# MCU_Board.net
KiCad netlist of a schematic drawn in Altium Designer
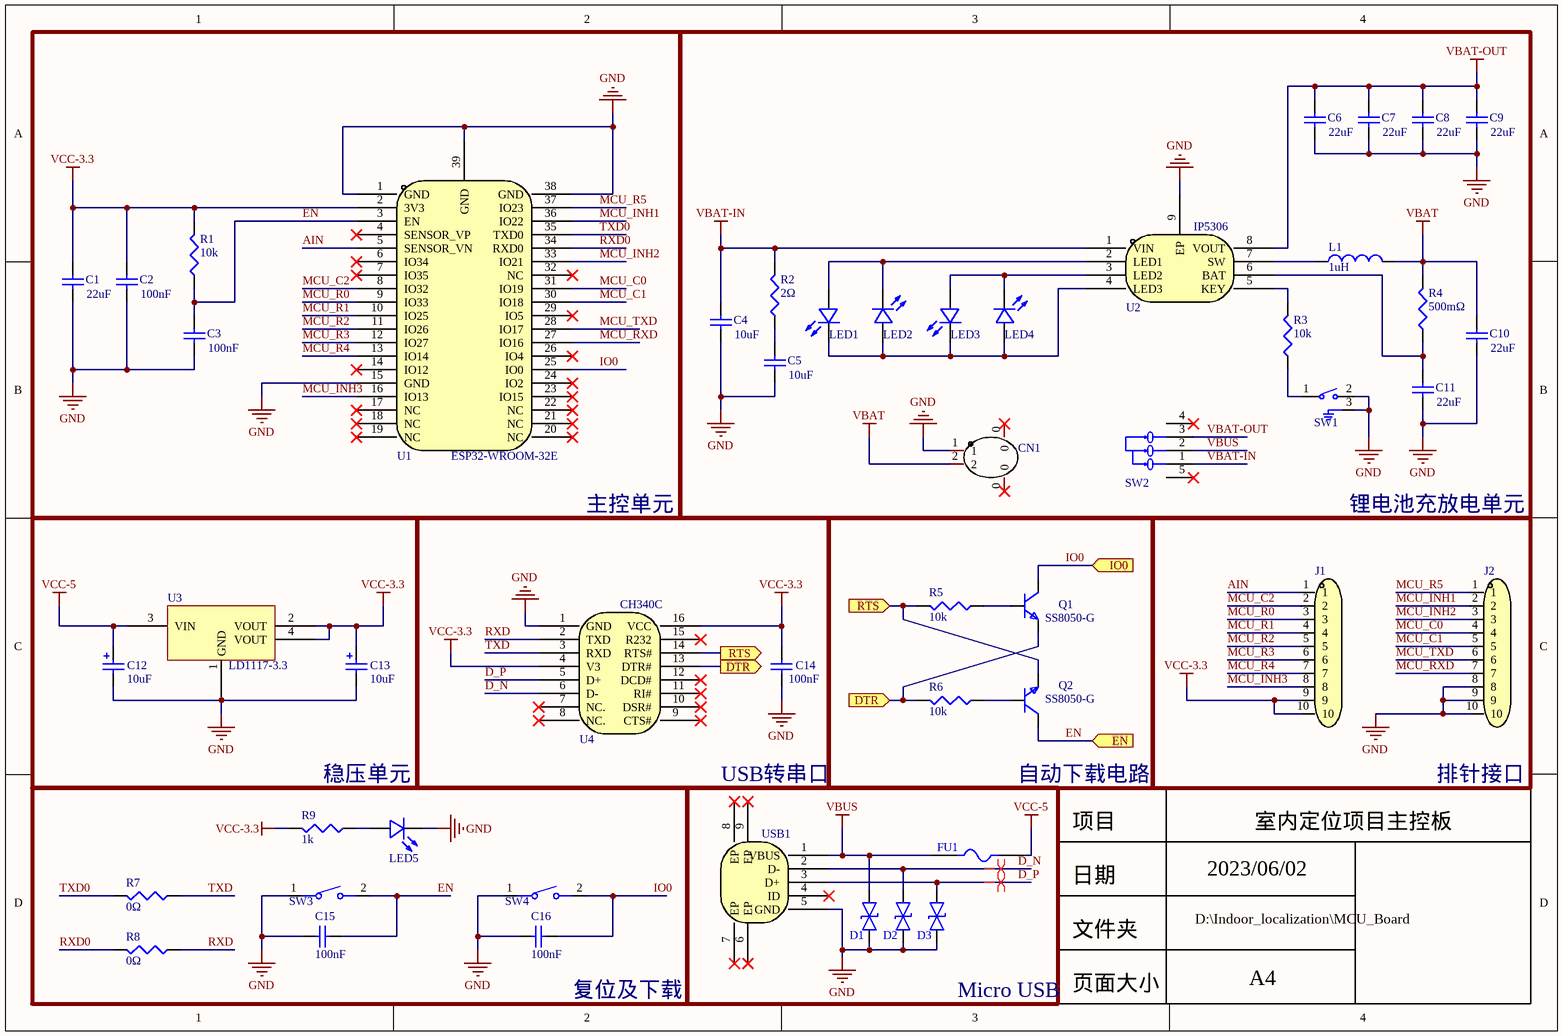
[diagram p0: MCU_Board.SchDoc]

(export (version "E")
  (design (tool "Eeschema 10.0.6"))
  (components
    (comp (ref "C1")
      (value "22uF")
      (footprint "C0603")
      (description "Capacitor")
      (fields (field (name "Comment") "Cap") (field (name "PUBLISHER") "Altium Limited"))
      (libsource (lib "Miscellaneous Devices") (part "Cap"))
    )
    (comp (ref "C2")
      (value "100nF")
      (footprint "C0603")
      (description "Capacitor")
      (fields (field (name "Comment") "Cap") (field (name "PUBLISHER") "Altium Limited"))
      (libsource (lib "Miscellaneous Devices") (part "Cap"))
    )
    (comp (ref "C3")
      (value "100nF")
      (footprint "C0603")
      (description "Capacitor")
      (fields (field (name "Comment") "Cap") (field (name "PUBLISHER") "Altium Limited"))
      (libsource (lib "Miscellaneous Devices") (part "Cap"))
    )
    (comp (ref "C4")
      (value "10uF")
      (footprint "C0603")
      (description "Capacitor")
      (fields (field (name "Comment") "Cap") (field (name "PUBLISHER") "Altium Limited"))
      (libsource (lib "Miscellaneous Devices") (part "Cap"))
    )
    (comp (ref "C5")
      (value "10uF")
      (footprint "C0603")
      (description "Capacitor")
      (fields (field (name "Comment") "Cap") (field (name "PUBLISHER") "Altium Limited"))
      (libsource (lib "Miscellaneous Devices") (part "Cap"))
    )
    (comp (ref "C6")
      (value "22uF")
      (footprint "C1206")
      (description "Capacitor")
      (fields (field (name "Comment") "Cap") (field (name "PUBLISHER") "Altium Limited"))
      (libsource (lib "Miscellaneous Devices") (part "Cap"))
    )
    (comp (ref "C7")
      (value "22uF")
      (footprint "C1206")
      (description "Capacitor")
      (fields (field (name "Comment") "Cap") (field (name "PUBLISHER") "Altium Limited"))
      (libsource (lib "Miscellaneous Devices") (part "Cap"))
    )
    (comp (ref "C8")
      (value "22uF")
      (footprint "C1206")
      (description "Capacitor")
      (fields (field (name "Comment") "Cap") (field (name "PUBLISHER") "Altium Limited"))
      (libsource (lib "Miscellaneous Devices") (part "Cap"))
    )
    (comp (ref "C9")
      (value "22uF")
      (footprint "C1206")
      (description "Capacitor")
      (fields (field (name "Comment") "Cap") (field (name "PUBLISHER") "Altium Limited"))
      (libsource (lib "Miscellaneous Devices") (part "Cap"))
    )
    (comp (ref "C10")
      (value "22uF")
      (footprint "C1206")
      (description "Capacitor")
      (fields (field (name "Comment") "Cap") (field (name "PUBLISHER") "Altium Limited"))
      (libsource (lib "Miscellaneous Devices") (part "Cap"))
    )
    (comp (ref "C11")
      (value "22uF")
      (footprint "C1206")
      (description "Capacitor")
      (fields (field (name "Comment") "Cap") (field (name "PUBLISHER") "Altium Limited"))
      (libsource (lib "Miscellaneous Devices") (part "Cap"))
    )
    (comp (ref "C12")
      (value "10uF")
      (footprint "CAP-SMD_L3.2-W1.6-RD-C7171")
      (description "贴片钽电容")
      (fields (field (name "MANUFACTURER") "Kyocera AVX") (field (name "MANUFACTURER PART") "TAJA106K016RNJ"))
      (libsource (lib "Passive_Device") (part "Cap-TAJA"))
    )
    (comp (ref "C13")
      (value "10uF")
      (footprint "CAP-SMD_L3.2-W1.6-RD-C7171")
      (description "贴片钽电容")
      (fields (field (name "MANUFACTURER") "Kyocera AVX") (field (name "MANUFACTURER PART") "TAJA106K016RNJ"))
      (libsource (lib "Passive_Device") (part "Cap-TAJA"))
    )
    (comp (ref "C14")
      (value "100nF")
      (footprint "C0603")
      (description "Capacitor")
      (fields (field (name "Comment") "Cap") (field (name "PUBLISHER") "Altium Limited"))
      (libsource (lib "Miscellaneous Devices") (part "Cap"))
    )
    (comp (ref "C15")
      (value "100nF")
      (footprint "C0603")
      (description "Capacitor")
      (fields (field (name "Comment") "Cap") (field (name "PUBLISHER") "Altium Limited"))
      (libsource (lib "Miscellaneous Devices") (part "Cap"))
    )
    (comp (ref "C16")
      (value "100nF")
      (footprint "C0603")
      (description "Capacitor")
      (fields (field (name "Comment") "Cap") (field (name "PUBLISHER") "Altium Limited"))
      (libsource (lib "Miscellaneous Devices") (part "Cap"))
    )
    (comp (ref "CN1")
      (value "1.0T-2P卧贴")
      (footprint "CONN-SMD_1.0T-2P")
      (description "锂电池接口")
      (fields (field (name "MANUFACTURER") "BOOMELE(博穆精密)"))
      (libsource (lib "Component") (part "1.0T-2P卧贴"))
    )
    (comp (ref "D1")
      (value "LESD5D5.0CT1G")
      (footprint "SOD-523_L1.2-W0.8-LS1.6-BI")
      (description "静电放电(ESD)保护器件")
      (fields (field (name "DESIGNER") "U?"))
      (libsource (lib "Passive_Device") (part "LESD5D5.0CT1G"))
    )
    (comp (ref "D2")
      (value "LESD5D5.0CT1G")
      (footprint "SOD-523_L1.2-W0.8-LS1.6-BI")
      (description "静电放电(ESD)保护器件")
      (fields (field (name "DESIGNER") "U?"))
      (libsource (lib "Passive_Device") (part "LESD5D5.0CT1G"))
    )
    (comp (ref "D3")
      (value "LESD5D5.0CT1G")
      (footprint "SOD-523_L1.2-W0.8-LS1.6-BI")
      (description "静电放电(ESD)保护器件")
      (fields (field (name "DESIGNER") "U?"))
      (libsource (lib "Passive_Device") (part "LESD5D5.0CT1G"))
    )
    (comp (ref "FU1")
      (value "FUSE 1A")
      (footprint "F0805")
      (description "贴片保险丝")
      (fields (field (name "MANUFACTURER") "RUILON(瑞隆源)") (field (name "MANUFACTURER PART") "SMD0805P075TF"))
      (libsource (lib "Passive_Device") (part "FU"))
    )
    (comp (ref "J1")
      (value "Header 10X1")
      (footprint "HDR-TH_10P-P2.54-V-M")
      (description "10P*1接插件")
      (fields (field (name "DESIGNER") "U?"))
      (libsource (lib "Connector") (part "Header 10X1"))
    )
    (comp (ref "J2")
      (value "Header 10X1")
      (footprint "HDR-TH_10P-P2.54-V-M")
      (description "10P*1接插件")
      (fields (field (name "DESIGNER") "U?"))
      (libsource (lib "Connector") (part "Header 10X1"))
    )
    (comp (ref "L1")
      (value "1uH")
      (footprint "IND-SMD_L6.5-W6.5_IHLP-2525")
      (description "Inductor")
      (fields (field (name "PUBLISHER") "Altium Limited"))
      (libsource (lib "Miscellaneous Devices") (part "Inductor"))
    )
    (comp (ref "LED1")
      (value "NCD0603G2")
      (footprint "LED0603-RD")
      (fields (field (name "MANUFACTURER") "国星光电"))
      (libsource (lib "Component") (part "NCD0603G2"))
    )
    (comp (ref "LED2")
      (value "NCD0603G2")
      (footprint "LED0603-RD")
      (fields (field (name "MANUFACTURER") "国星光电"))
      (libsource (lib "Component") (part "NCD0603G2"))
    )
    (comp (ref "LED3")
      (value "NCD0603G2")
      (footprint "LED0603-RD")
      (fields (field (name "MANUFACTURER") "国星光电"))
      (libsource (lib "Component") (part "NCD0603G2"))
    )
    (comp (ref "LED4")
      (value "NCD0603G2")
      (footprint "LED0603-RD")
      (fields (field (name "MANUFACTURER") "国星光电"))
      (libsource (lib "Component") (part "NCD0603G2"))
    )
    (comp (ref "LED5")
      (value "NCD0603G2")
      (footprint "LED0603-RD")
      (description "LED")
      (fields (field (name "MANUFACTURER") "国星光电"))
      (libsource (lib "Component") (part "NCD0603G2"))
    )
    (comp (ref "Q1")
      (value "SS8050-G")
      (footprint "SOT-23-3_L2.9-W1.3-P1.90-LS2.4-BR")
      (fields (field (name "MANUFACTURER") "CJ(江苏长电/长晶)"))
      (libsource (lib "Component") (part "SS8050-G"))
    )
    (comp (ref "Q2")
      (value "SS8050-G")
      (footprint "SOT-23-3_L2.9-W1.3-P1.90-LS2.4-BR")
      (fields (field (name "MANUFACTURER") "CJ(江苏长电/长晶)"))
      (libsource (lib "Component") (part "SS8050-G"))
    )
    (comp (ref "R1")
      (value "10k")
      (footprint "R0603")
      (description "Resistor")
      (fields (field (name "PUBLISHER") "Altium Limited"))
      (libsource (lib "Miscellaneous Devices") (part "Res3"))
    )
    (comp (ref "R2")
      (value "2Ω")
      (footprint "R0603")
      (description "Resistor")
      (fields (field (name "PUBLISHER") "Altium Limited"))
      (libsource (lib "Miscellaneous Devices") (part "Res3"))
    )
    (comp (ref "R3")
      (value "10k")
      (footprint "R0603")
      (description "Resistor")
      (fields (field (name "PUBLISHER") "Altium Limited"))
      (libsource (lib "Miscellaneous Devices") (part "Res3"))
    )
    (comp (ref "R4")
      (value "500mΩ")
      (footprint "R0603")
      (description "Resistor")
      (fields (field (name "PUBLISHER") "Altium Limited"))
      (libsource (lib "Miscellaneous Devices") (part "Res3"))
    )
    (comp (ref "R5")
      (value "10k")
      (footprint "R0603")
      (description "Resistor")
      (fields (field (name "PUBLISHER") "Altium Limited"))
      (libsource (lib "Miscellaneous Devices") (part "Res3"))
    )
    (comp (ref "R6")
      (value "10k")
      (footprint "R0603")
      (description "Resistor")
      (fields (field (name "PUBLISHER") "Altium Limited"))
      (libsource (lib "Miscellaneous Devices") (part "Res3"))
    )
    (comp (ref "R7")
      (value "0Ω")
      (footprint "R0603")
      (description "Resistor")
      (fields (field (name "PUBLISHER") "Altium Limited"))
      (libsource (lib "Miscellaneous Devices") (part "Res3"))
    )
    (comp (ref "R8")
      (value "0Ω")
      (footprint "R0603")
      (description "Resistor")
      (fields (field (name "PUBLISHER") "Altium Limited"))
      (libsource (lib "Miscellaneous Devices") (part "Res3"))
    )
    (comp (ref "R9")
      (value "1k")
      (footprint "R0603")
      (description "Resistor")
      (fields (field (name "PUBLISHER") "Altium Limited"))
      (libsource (lib "Miscellaneous Devices") (part "Res3"))
    )
    (comp (ref "SW1")
      (value "GT-TCB73B-H048-L1")
      (footprint "SW-TH_G-SWITCH_GT-TCB73B-H048-L1")
      (fields (field (name "MANUFACTURER") "G-Switch(品赞)"))
      (libsource (lib "Component") (part "GT-TCB73B-H048-L1"))
    )
    (comp (ref "SW2")
      (value "SK12D07VG3")
      (footprint "SW-TH_SK12D07VG3")
      (fields (field (name "MANUFACTURER") "SHOU HAN(首韩)"))
      (libsource (lib "Component") (part "SK12D07VG3"))
    )
    (comp (ref "SW3")
      (value "TS-1088-AR02016")
      (footprint "SW-SMD_L3.9-W3.0-P4.45")
      (fields (field (name "MANUFACTURER") "XUNPU(讯普)"))
      (libsource (lib "Component") (part "TS-1088-AR02016"))
    )
    (comp (ref "SW4")
      (value "TS-1088-AR02016")
      (footprint "SW-SMD_L3.9-W3.0-P4.45")
      (fields (field (name "MANUFACTURER") "XUNPU(讯普)"))
      (libsource (lib "Component") (part "TS-1088-AR02016"))
    )
    (comp (ref "U1")
      (value "ESP32-WROOM-32E")
      (footprint "WIFI-SMD_ESP32-WROOM-32E")
      (fields
        (field (name "MANUFACTURER") "ESPRESSIF(乐鑫)")
        (field (name "MANUFACTURER PART") "ESP32-WROOM-32E-N16")
      )
      (libsource (lib "Component") (part "ESP32-WROOM-32E-N16_C701343"))
    )
    (comp (ref "U2")
      (value "IP5306")
      (footprint "ESOP-8_L4.9-W3.9-P1.27-LS6.0-BL-EP")
      (fields (field (name "MANUFACTURER") "INJOINIC(英集芯)"))
      (libsource (lib "Component") (part "IP5306"))
    )
    (comp (ref "U3")
      (value "LD1117-3.3")
      (footprint "SOT-223-3_L6.5-W3.4-P2.30-LS7.0-BR")
      (description "低压差线性稳压器3.3V")
      (libsource (lib "Power") (part "LD1117-3.3"))
    )
    (comp (ref "U4")
      (value "CH340C")
      (footprint "SOP-16_L10.0-W3.9-P1.27-LS6.0-BL")
      (fields (field (name "MANUFACTURER") "WCH(南京沁恒)"))
      (libsource (lib "Component") (part "CH340C"))
    )
    (comp (ref "USB1")
      (value "U-F-M5DD-W-2")
      (footprint "MICRO-USB-SMD_MICRO-USB-A17")
      (fields (field (name "MANUFACTURER") "韩国韩荣"))
      (libsource (lib "Component") (part "U-F-M5DD-W-2"))
    )
  )
  (nets
    (net (code "2") (name "/AIN") (class "Default")
      (node (ref "J1") (pin "1") (pinfunction "1_1") (pintype "passive"))
      (node (ref "U1") (pin "5") (pinfunction "SENSOR_VN_5") (pintype "passive"))
    )
    (net (code "3") (name "/DTR") (class "Default")
      (node (ref "Q1") (pin "2") (pinfunction "E_2") (pintype "passive"))
      (node (ref "R6") (pin "2") (pinfunction "2_2") (pintype "passive"))
      (node (ref "U4") (pin "13") (pinfunction "DTR#_13") (pintype "passive"))
    )
    (net (code "4") (name "/D_N") (class "Default")
      (node (ref "D2") (pin "2") (pinfunction "2_2") (pintype "passive"))
      (node (ref "U4") (pin "6") (pinfunction "D-_6") (pintype "passive"))
      (node (ref "USB1") (pin "2") (pinfunction "D-_2") (pintype "passive"))
    )
    (net (code "5") (name "/D_P") (class "Default")
      (node (ref "D3") (pin "2") (pinfunction "2_2") (pintype "passive"))
      (node (ref "U4") (pin "5") (pinfunction "D+_5") (pintype "passive"))
      (node (ref "USB1") (pin "3") (pinfunction "D+_3") (pintype "passive"))
    )
    (net (code "6") (name "/EN") (class "Default")
      (node (ref "C15") (pin "1") (pinfunction "1_1") (pintype "passive"))
      (node (ref "C3") (pin "2") (pinfunction "2_2") (pintype "passive"))
      (node (ref "Q2") (pin "3") (pinfunction "C_3") (pintype "passive"))
      (node (ref "R1") (pin "1") (pinfunction "1_1") (pintype "passive"))
      (node (ref "SW3") (pin "2") (pinfunction "2_2") (pintype "passive"))
      (node (ref "U1") (pin "3") (pinfunction "EN_3") (pintype "passive"))
    )
    (net (code "7") (name "/IO0") (class "Default")
      (node (ref "C16") (pin "1") (pinfunction "1_1") (pintype "passive"))
      (node (ref "Q1") (pin "3") (pinfunction "C_3") (pintype "passive"))
      (node (ref "SW4") (pin "2") (pinfunction "2_2") (pintype "passive"))
      (node (ref "U1") (pin "25") (pinfunction "IO0_25") (pintype "passive"))
    )
    (net (code "8") (name "/MCU_C0") (class "Default")
      (node (ref "J2") (pin "4") (pinfunction "4_4") (pintype "passive"))
      (node (ref "U1") (pin "31") (pinfunction "IO19_31") (pintype "passive"))
    )
    (net (code "9") (name "/MCU_C1") (class "Default")
      (node (ref "J2") (pin "5") (pinfunction "5_5") (pintype "passive"))
      (node (ref "U1") (pin "30") (pinfunction "IO18_30") (pintype "passive"))
    )
    (net (code "10") (name "/MCU_C2") (class "Default")
      (node (ref "J1") (pin "2") (pinfunction "2_2") (pintype "passive"))
      (node (ref "U1") (pin "8") (pinfunction "IO32_8") (pintype "passive"))
    )
    (net (code "11") (name "/MCU_INH1") (class "Default")
      (node (ref "J2") (pin "2") (pinfunction "2_2") (pintype "passive"))
      (node (ref "U1") (pin "36") (pinfunction "IO22_36") (pintype "passive"))
    )
    (net (code "12") (name "/MCU_INH2") (class "Default")
      (node (ref "J2") (pin "3") (pinfunction "3_3") (pintype "passive"))
      (node (ref "U1") (pin "33") (pinfunction "IO21_33") (pintype "passive"))
    )
    (net (code "13") (name "/MCU_INH3") (class "Default")
      (node (ref "J1") (pin "8") (pinfunction "8_8") (pintype "passive"))
      (node (ref "U1") (pin "16") (pinfunction "IO13_16") (pintype "passive"))
    )
    (net (code "14") (name "/MCU_R0") (class "Default")
      (node (ref "J1") (pin "3") (pinfunction "3_3") (pintype "passive"))
      (node (ref "U1") (pin "9") (pinfunction "IO33_9") (pintype "passive"))
    )
    (net (code "15") (name "/MCU_R1") (class "Default")
      (node (ref "J1") (pin "4") (pinfunction "4_4") (pintype "passive"))
      (node (ref "U1") (pin "10") (pinfunction "IO25_10") (pintype "passive"))
    )
    (net (code "16") (name "/MCU_R2") (class "Default")
      (node (ref "J1") (pin "5") (pinfunction "5_5") (pintype "passive"))
      (node (ref "U1") (pin "11") (pinfunction "IO26_11") (pintype "passive"))
    )
    (net (code "17") (name "/MCU_R3") (class "Default")
      (node (ref "J1") (pin "6") (pinfunction "6_6") (pintype "passive"))
      (node (ref "U1") (pin "12") (pinfunction "IO27_12") (pintype "passive"))
    )
    (net (code "18") (name "/MCU_R4") (class "Default")
      (node (ref "J1") (pin "7") (pinfunction "7_7") (pintype "passive"))
      (node (ref "U1") (pin "13") (pinfunction "IO14_13") (pintype "passive"))
    )
    (net (code "19") (name "/MCU_R5") (class "Default")
      (node (ref "J2") (pin "1") (pinfunction "1_1") (pintype "passive"))
      (node (ref "U1") (pin "37") (pinfunction "IO23_37") (pintype "passive"))
    )
    (net (code "20") (name "/MCU_RXD") (class "Default")
      (node (ref "J2") (pin "7") (pinfunction "7_7") (pintype "passive"))
      (node (ref "U1") (pin "27") (pinfunction "IO16_27") (pintype "passive"))
    )
    (net (code "21") (name "/MCU_TXD") (class "Default")
      (node (ref "J2") (pin "6") (pinfunction "6_6") (pintype "passive"))
      (node (ref "U1") (pin "28") (pinfunction "IO17_28") (pintype "passive"))
    )
    (net (code "22") (name "/RTS") (class "Default")
      (node (ref "Q2") (pin "2") (pinfunction "E_2") (pintype "passive"))
      (node (ref "R5") (pin "2") (pinfunction "2_2") (pintype "passive"))
      (node (ref "U4") (pin "14") (pinfunction "RTS#_14") (pintype "passive"))
    )
    (net (code "23") (name "/RXD") (class "Default")
      (node (ref "R8") (pin "1") (pinfunction "1_1") (pintype "passive"))
      (node (ref "U4") (pin "2") (pinfunction "TXD_2") (pintype "passive"))
    )
    (net (code "24") (name "/RXD0") (class "Default")
      (node (ref "R8") (pin "2") (pinfunction "2_2") (pintype "passive"))
      (node (ref "U1") (pin "34") (pinfunction "RXD0_34") (pintype "passive"))
    )
    (net (code "25") (name "/TXD") (class "Default")
      (node (ref "R7") (pin "1") (pinfunction "1_1") (pintype "passive"))
      (node (ref "U4") (pin "3") (pinfunction "RXD_3") (pintype "passive"))
    )
    (net (code "26") (name "/TXD0") (class "Default")
      (node (ref "R7") (pin "2") (pinfunction "2_2") (pintype "passive"))
      (node (ref "U1") (pin "35") (pinfunction "TXD0_35") (pintype "passive"))
    )
    (net (code "27") (name "GND") (class "Default")
      (node (ref "C1") (pin "1") (pinfunction "1_1") (pintype "passive"))
      (node (ref "C10") (pin "1") (pinfunction "1_1") (pintype "passive"))
      (node (ref "C11") (pin "1") (pinfunction "1_1") (pintype "passive"))
      (node (ref "C12") (pin "2") (pinfunction "2_2") (pintype "passive"))
      (node (ref "C13") (pin "2") (pinfunction "2_2") (pintype "passive"))
      (node (ref "C14") (pin "2") (pinfunction "2_2") (pintype "passive"))
      (node (ref "C15") (pin "2") (pinfunction "2_2") (pintype "passive"))
      (node (ref "C16") (pin "2") (pinfunction "2_2") (pintype "passive"))
      (node (ref "C2") (pin "1") (pinfunction "1_1") (pintype "passive"))
      (node (ref "C3") (pin "1") (pinfunction "1_1") (pintype "passive"))
      (node (ref "C4") (pin "1") (pinfunction "1_1") (pintype "passive"))
      (node (ref "C5") (pin "1") (pinfunction "1_1") (pintype "passive"))
      (node (ref "C6") (pin "1") (pinfunction "1_1") (pintype "passive"))
      (node (ref "C7") (pin "1") (pinfunction "1_1") (pintype "passive"))
      (node (ref "C8") (pin "1") (pinfunction "1_1") (pintype "passive"))
      (node (ref "C9") (pin "1") (pinfunction "1_1") (pintype "passive"))
      (node (ref "CN1") (pin "1") (pinfunction "1_1") (pintype "passive"))
      (node (ref "D1") (pin "1") (pinfunction "1_1") (pintype "passive"))
      (node (ref "D2") (pin "1") (pinfunction "1_1") (pintype "passive"))
      (node (ref "D3") (pin "1") (pinfunction "1_1") (pintype "passive"))
      (node (ref "J2") (pin "10") (pinfunction "10_10") (pintype "passive"))
      (node (ref "J2") (pin "8") (pinfunction "8_8") (pintype "passive"))
      (node (ref "J2") (pin "9") (pinfunction "9_9") (pintype "passive"))
      (node (ref "LED5") (pin "1") (pinfunction "K_1") (pintype "passive"))
      (node (ref "SW1") (pin "2") (pinfunction "2_2") (pintype "passive"))
      (node (ref "SW1") (pin "3") (pinfunction "3_3") (pintype "passive"))
      (node (ref "SW3") (pin "1") (pinfunction "1_1") (pintype "passive"))
      (node (ref "SW4") (pin "1") (pinfunction "1_1") (pintype "passive"))
      (node (ref "U1") (pin "1") (pinfunction "GND_1") (pintype "passive"))
      (node (ref "U1") (pin "15") (pinfunction "GND_15") (pintype "passive"))
      (node (ref "U1") (pin "38") (pinfunction "GND_38") (pintype "passive"))
      (node (ref "U1") (pin "39") (pinfunction "GND_39") (pintype "passive"))
      (node (ref "U2") (pin "9") (pinfunction "EP_9") (pintype "passive"))
      (node (ref "U3") (pin "1") (pinfunction "GND_1") (pintype "passive"))
      (node (ref "U4") (pin "1") (pinfunction "GND_1") (pintype "passive"))
      (node (ref "USB1") (pin "5") (pinfunction "GND_5") (pintype "passive"))
    )
    (net (code "28") (name "Net-(C5-Pad2)") (class "Default")
      (node (ref "C5") (pin "2") (pinfunction "2_2") (pintype "passive"))
      (node (ref "R2") (pin "1") (pinfunction "1_1") (pintype "passive"))
    )
    (net (code "29") (name "Net-(LED1-A)") (class "Default")
      (node (ref "LED1") (pin "2") (pinfunction "A_2") (pintype "passive"))
      (node (ref "LED2") (pin "1") (pinfunction "K_1") (pintype "passive"))
      (node (ref "U2") (pin "2") (pinfunction "LED1_2") (pintype "passive"))
    )
    (net (code "30") (name "Net-(LED1-K)") (class "Default")
      (node (ref "LED1") (pin "1") (pinfunction "K_1") (pintype "passive"))
      (node (ref "LED2") (pin "2") (pinfunction "A_2") (pintype "passive"))
      (node (ref "LED3") (pin "1") (pinfunction "K_1") (pintype "passive"))
      (node (ref "LED4") (pin "2") (pinfunction "A_2") (pintype "passive"))
      (node (ref "U2") (pin "4") (pinfunction "LED3_4") (pintype "passive"))
    )
    (net (code "31") (name "Net-(LED3-A)") (class "Default")
      (node (ref "LED3") (pin "2") (pinfunction "A_2") (pintype "passive"))
      (node (ref "LED4") (pin "1") (pinfunction "K_1") (pintype "passive"))
      (node (ref "U2") (pin "3") (pinfunction "LED2_3") (pintype "passive"))
    )
    (net (code "32") (name "Net-(LED5-A)") (class "Default")
      (node (ref "LED5") (pin "2") (pinfunction "A_2") (pintype "passive"))
      (node (ref "R9") (pin "1") (pinfunction "1_1") (pintype "passive"))
    )
    (net (code "33") (name "Net-(Q1-B)") (class "Default")
      (node (ref "Q1") (pin "1") (pinfunction "B_1") (pintype "passive"))
      (node (ref "R5") (pin "1") (pinfunction "1_1") (pintype "passive"))
    )
    (net (code "34") (name "Net-(Q2-B)") (class "Default")
      (node (ref "Q2") (pin "1") (pinfunction "B_1") (pintype "passive"))
      (node (ref "R6") (pin "1") (pinfunction "1_1") (pintype "passive"))
    )
    (net (code "35") (name "Net-(R3-Pad1)") (class "Default")
      (node (ref "R3") (pin "1") (pinfunction "1_1") (pintype "passive"))
      (node (ref "SW1") (pin "1") (pinfunction "1_1") (pintype "passive"))
    )
    (net (code "36") (name "Net-(U2-BAT)") (class "Default")
      (node (ref "C11") (pin "2") (pinfunction "2_2") (pintype "passive"))
      (node (ref "R4") (pin "1") (pinfunction "1_1") (pintype "passive"))
      (node (ref "U2") (pin "6") (pinfunction "BAT_6") (pintype "passive"))
    )
    (net (code "37") (name "Net-(U2-KEY)") (class "Default")
      (node (ref "R3") (pin "2") (pinfunction "2_2") (pintype "passive"))
      (node (ref "U2") (pin "5") (pinfunction "KEY_5") (pintype "passive"))
    )
    (net (code "38") (name "Net-(U2-SW)") (class "Default")
      (node (ref "L1") (pin "1") (pinfunction "1_1") (pintype "passive"))
      (node (ref "U2") (pin "7") (pinfunction "SW_7") (pintype "passive"))
    )
    (net (code "39") (name "VBAT") (class "Default")
      (node (ref "C10") (pin "2") (pinfunction "2_2") (pintype "passive"))
      (node (ref "CN1") (pin "2") (pinfunction "2_2") (pintype "passive"))
      (node (ref "L1") (pin "2") (pinfunction "2_2") (pintype "passive"))
      (node (ref "R4") (pin "2") (pinfunction "2_2") (pintype "passive"))
    )
    (net (code "40") (name "VBAT-IN") (class "Default")
      (node (ref "C4") (pin "2") (pinfunction "2_2") (pintype "passive"))
      (node (ref "R2") (pin "2") (pinfunction "2_2") (pintype "passive"))
      (node (ref "SW2") (pin "1") (pinfunction "1_1") (pintype "passive"))
      (node (ref "U2") (pin "1") (pinfunction "VIN_1") (pintype "passive"))
    )
    (net (code "41") (name "VBAT-OUT") (class "Default")
      (node (ref "C6") (pin "2") (pinfunction "2_2") (pintype "passive"))
      (node (ref "C7") (pin "2") (pinfunction "2_2") (pintype "passive"))
      (node (ref "C8") (pin "2") (pinfunction "2_2") (pintype "passive"))
      (node (ref "C9") (pin "2") (pinfunction "2_2") (pintype "passive"))
      (node (ref "SW2") (pin "3") (pinfunction "3_3") (pintype "passive"))
      (node (ref "U2") (pin "8") (pinfunction "VOUT_8") (pintype "passive"))
    )
    (net (code "42") (name "VBUS") (class "Default")
      (node (ref "D1") (pin "2") (pinfunction "2_2") (pintype "passive"))
      (node (ref "FU1") (pin "1") (pinfunction "1_1") (pintype "passive"))
      (node (ref "SW2") (pin "2") (pinfunction "2_2") (pintype "passive"))
      (node (ref "USB1") (pin "1") (pinfunction "VBUS_1") (pintype "passive"))
    )
    (net (code "43") (name "VCC-3.3") (class "Default")
      (node (ref "C1") (pin "2") (pinfunction "2_2") (pintype "passive"))
      (node (ref "C13") (pin "1") (pinfunction "1_1") (pintype "passive"))
      (node (ref "C14") (pin "1") (pinfunction "1_1") (pintype "passive"))
      (node (ref "C2") (pin "2") (pinfunction "2_2") (pintype "passive"))
      (node (ref "J1") (pin "10") (pinfunction "10_10") (pintype "passive"))
      (node (ref "J1") (pin "9") (pinfunction "9_9") (pintype "passive"))
      (node (ref "R1") (pin "2") (pinfunction "2_2") (pintype "passive"))
      (node (ref "R9") (pin "2") (pinfunction "2_2") (pintype "passive"))
      (node (ref "U1") (pin "2") (pinfunction "3V3_2") (pintype "passive"))
      (node (ref "U3") (pin "2") (pinfunction "VOUT_2") (pintype "passive"))
      (node (ref "U3") (pin "4") (pinfunction "VOUT_4") (pintype "passive"))
      (node (ref "U4") (pin "16") (pinfunction "VCC_16") (pintype "passive"))
      (node (ref "U4") (pin "4") (pinfunction "V3_4") (pintype "passive"))
    )
    (net (code "44") (name "VCC-5") (class "Default")
      (node (ref "C12") (pin "1") (pinfunction "1_1") (pintype "passive"))
      (node (ref "FU1") (pin "2") (pinfunction "2_2") (pintype "passive"))
      (node (ref "U3") (pin "3") (pinfunction "VIN_3") (pintype "passive"))
    )
    (net (code "45") (name "unconnected-(CN1-Pad0)") (class "Default")
      (node (ref "CN1") (pin "0") (pinfunction "0_0") (pintype "passive+no_connect"))
    )
    (net (code "46") (name "unconnected-(CN1-Pad0)_1") (class "Default")
      (node (ref "CN1") (pin "0") (pinfunction "0_0") (pintype "passive+no_connect"))
    )
    (net (code "47") (name "unconnected-(SW2-Pad4)") (class "Default")
      (node (ref "SW2") (pin "4") (pinfunction "4_4") (pintype "passive+no_connect"))
    )
    (net (code "48") (name "unconnected-(SW2-Pad5)") (class "Default")
      (node (ref "SW2") (pin "5") (pinfunction "5_5") (pintype "passive+no_connect"))
    )
    (net (code "49") (name "unconnected-(U1-IO2-Pad24)") (class "Default")
      (node (ref "U1") (pin "24") (pinfunction "IO2_24") (pintype "passive+no_connect"))
    )
    (net (code "50") (name "unconnected-(U1-IO4-Pad26)") (class "Default")
      (node (ref "U1") (pin "26") (pinfunction "IO4_26") (pintype "passive+no_connect"))
    )
    (net (code "51") (name "unconnected-(U1-IO5-Pad29)") (class "Default")
      (node (ref "U1") (pin "29") (pinfunction "IO5_29") (pintype "passive+no_connect"))
    )
    (net (code "52") (name "unconnected-(U1-IO12-Pad14)") (class "Default")
      (node (ref "U1") (pin "14") (pinfunction "IO12_14") (pintype "passive+no_connect"))
    )
    (net (code "53") (name "unconnected-(U1-IO15-Pad23)") (class "Default")
      (node (ref "U1") (pin "23") (pinfunction "IO15_23") (pintype "passive+no_connect"))
    )
    (net (code "54") (name "unconnected-(U1-IO34-Pad6)") (class "Default")
      (node (ref "U1") (pin "6") (pinfunction "IO34_6") (pintype "passive+no_connect"))
    )
    (net (code "55") (name "unconnected-(U1-IO35-Pad7)") (class "Default")
      (node (ref "U1") (pin "7") (pinfunction "IO35_7") (pintype "passive+no_connect"))
    )
    (net (code "56") (name "unconnected-(U1-NC-Pad17)") (class "Default")
      (node (ref "U1") (pin "17") (pinfunction "NC_17") (pintype "passive+no_connect"))
    )
    (net (code "57") (name "unconnected-(U1-NC-Pad18)") (class "Default")
      (node (ref "U1") (pin "18") (pinfunction "NC_18") (pintype "passive+no_connect"))
    )
    (net (code "58") (name "unconnected-(U1-NC-Pad19)") (class "Default")
      (node (ref "U1") (pin "19") (pinfunction "NC_19") (pintype "passive+no_connect"))
    )
    (net (code "59") (name "unconnected-(U1-NC-Pad20)") (class "Default")
      (node (ref "U1") (pin "20") (pinfunction "NC_20") (pintype "passive+no_connect"))
    )
    (net (code "60") (name "unconnected-(U1-NC-Pad21)") (class "Default")
      (node (ref "U1") (pin "21") (pinfunction "NC_21") (pintype "passive+no_connect"))
    )
    (net (code "61") (name "unconnected-(U1-NC-Pad22)") (class "Default")
      (node (ref "U1") (pin "22") (pinfunction "NC_22") (pintype "passive+no_connect"))
    )
    (net (code "62") (name "unconnected-(U1-NC-Pad32)") (class "Default")
      (node (ref "U1") (pin "32") (pinfunction "NC_32") (pintype "passive+no_connect"))
    )
    (net (code "63") (name "unconnected-(U1-SENSOR_VP-Pad4)") (class "Default")
      (node (ref "U1") (pin "4") (pinfunction "SENSOR_VP_4") (pintype "passive+no_connect"))
    )
    (net (code "64") (name "unconnected-(U4-CTS#-Pad9)") (class "Default")
      (node (ref "U4") (pin "9") (pinfunction "CTS#_9") (pintype "passive+no_connect"))
    )
    (net (code "65") (name "unconnected-(U4-DCD#-Pad12)") (class "Default")
      (node (ref "U4") (pin "12") (pinfunction "DCD#_12") (pintype "passive+no_connect"))
    )
    (net (code "66") (name "unconnected-(U4-DSR#-Pad10)") (class "Default")
      (node (ref "U4") (pin "10") (pinfunction "DSR#_10") (pintype "passive+no_connect"))
    )
    (net (code "67") (name "unconnected-(U4-NC.-Pad7)") (class "Default")
      (node (ref "U4") (pin "7") (pinfunction "NC._7") (pintype "passive+no_connect"))
    )
    (net (code "68") (name "unconnected-(U4-NC.-Pad8)") (class "Default")
      (node (ref "U4") (pin "8") (pinfunction "NC._8") (pintype "passive+no_connect"))
    )
    (net (code "69") (name "unconnected-(U4-R232-Pad15)") (class "Default")
      (node (ref "U4") (pin "15") (pinfunction "R232_15") (pintype "passive+no_connect"))
    )
    (net (code "70") (name "unconnected-(U4-RI#-Pad11)") (class "Default")
      (node (ref "U4") (pin "11") (pinfunction "RI#_11") (pintype "passive+no_connect"))
    )
    (net (code "71") (name "unconnected-(USB1-EP-Pad6)") (class "Default")
      (node (ref "USB1") (pin "6") (pinfunction "EP_6") (pintype "passive+no_connect"))
    )
    (net (code "72") (name "unconnected-(USB1-EP-Pad7)") (class "Default")
      (node (ref "USB1") (pin "7") (pinfunction "EP_7") (pintype "passive+no_connect"))
    )
    (net (code "73") (name "unconnected-(USB1-EP-Pad8)") (class "Default")
      (node (ref "USB1") (pin "8") (pinfunction "EP_8") (pintype "passive+no_connect"))
    )
    (net (code "74") (name "unconnected-(USB1-EP-Pad9)") (class "Default")
      (node (ref "USB1") (pin "9") (pinfunction "EP_9") (pintype "passive+no_connect"))
    )
    (net (code "75") (name "unconnected-(USB1-ID-Pad4)") (class "Default")
      (node (ref "USB1") (pin "4") (pinfunction "ID_4") (pintype "passive+no_connect"))
    )
  )
)
